# 03_Mos.net
KiCad netlist of a schematic drawn in Altium Designer
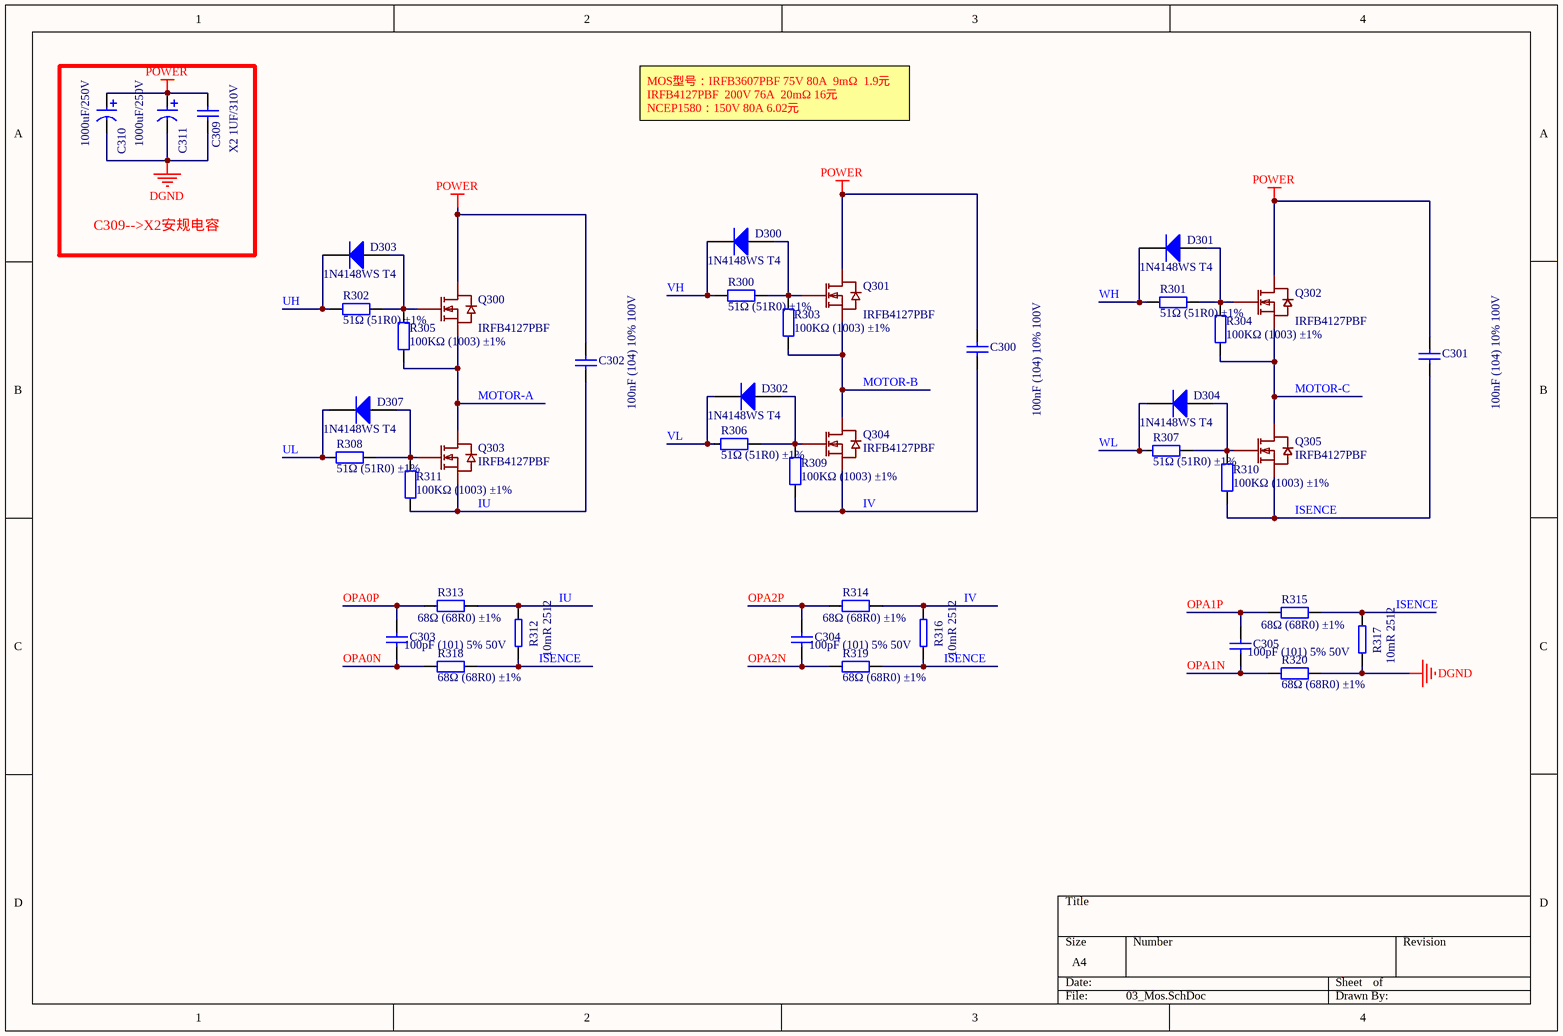
[diagram p0: 03_Mos.SchDoc]

(export (version "E")
  (design (tool "Eeschema 10.0.6"))
  (components
    (comp (ref "C300")
      (value "100nF (104) 10% 100V")
      (footprint "1206_C")
      (description "贴片电容")
      (libsource (lib "Miscellaneous Devices LC") (part "1206 100nF (104) 10% 50V"))
    )
    (comp (ref "C301")
      (value "100nF (104) 10% 100V")
      (footprint "1206_C")
      (description "贴片电容")
      (libsource (lib "Miscellaneous Devices LC") (part "1206 100nF (104) 10% 50V"))
    )
    (comp (ref "C302")
      (value "100nF (104) 10% 100V")
      (footprint "1206_C")
      (description "贴片电容")
      (libsource (lib "Miscellaneous Devices LC") (part "1206 100nF (104) 10% 50V"))
    )
    (comp (ref "C303")
      (value "100pF (101) 5% 50V")
      (footprint "0805_C")
      (description "贴片电容")
      (libsource (lib "Miscellaneous Devices LC") (part "0805 100pF (101) 5% 50V"))
    )
    (comp (ref "C304")
      (value "100pF (101) 5% 50V")
      (footprint "0805_C")
      (description "贴片电容")
      (libsource (lib "Miscellaneous Devices LC") (part "0805 100pF (101) 5% 50V"))
    )
    (comp (ref "C305")
      (value "100pF (101) 5% 50V")
      (footprint "0805_C")
      (description "贴片电容")
      (libsource (lib "Miscellaneous Devices LC") (part "0805 100pF (101) 5% 50V"))
    )
    (comp (ref "C309")
      (value "X2 1UF/310V")
      (footprint "X2 1UF 310V")
      (description "贴片电容")
      (libsource (lib "Miscellaneous Devices LC") (part "1206 100nF (104) 10% 50V"))
    )
    (comp (ref "C310")
      (value "1000uF/250V")
      (footprint "1000uf/250V")
      (description "电解电容")
      (libsource (lib "Schlibv2") (part "CAP2"))
    )
    (comp (ref "C311")
      (value "1000uF/250V")
      (footprint "1000uf/250V")
      (description "电解电容")
      (libsource (lib "Schlibv2") (part "CAP2"))
    )
    (comp (ref "D300")
      (value "1N4148WS T4")
      (footprint "SOD-323")
      (description "二极管")
      (libsource (lib "Miscellaneous Devices LC") (part "SOD-323 1N4148WS T4"))
    )
    (comp (ref "D301")
      (value "1N4148WS T4")
      (footprint "SOD-323")
      (description "二极管")
      (libsource (lib "Miscellaneous Devices LC") (part "SOD-323 1N4148WS T4"))
    )
    (comp (ref "D302")
      (value "1N4148WS T4")
      (footprint "SOD-323")
      (description "二极管")
      (libsource (lib "Miscellaneous Devices LC") (part "SOD-323 1N4148WS T4"))
    )
    (comp (ref "D303")
      (value "1N4148WS T4")
      (footprint "SOD-323")
      (description "二极管")
      (libsource (lib "Miscellaneous Devices LC") (part "SOD-323 1N4148WS T4"))
    )
    (comp (ref "D304")
      (value "1N4148WS T4")
      (footprint "SOD-323")
      (description "二极管")
      (libsource (lib "Miscellaneous Devices LC") (part "SOD-323 1N4148WS T4"))
    )
    (comp (ref "D307")
      (value "1N4148WS T4")
      (footprint "SOD-323")
      (description "二极管")
      (libsource (lib "Miscellaneous Devices LC") (part "SOD-323 1N4148WS T4"))
    )
    (comp (ref "Q300")
      (value "IRFB4127PBF")
      (footprint "IRFB4127")
      (libsource (lib "RayPCB20210502") (part "IRFB4127PBF"))
    )
    (comp (ref "Q301")
      (value "IRFB4127PBF")
      (footprint "IRFB4127")
      (libsource (lib "RayPCB20210502") (part "IRFB4127PBF"))
    )
    (comp (ref "Q302")
      (value "IRFB4127PBF")
      (footprint "IRFB4127")
      (libsource (lib "RayPCB20210502") (part "IRFB4127PBF"))
    )
    (comp (ref "Q303")
      (value "IRFB4127PBF")
      (footprint "IRFB4127")
      (libsource (lib "RayPCB20210502") (part "IRFB4127PBF"))
    )
    (comp (ref "Q304")
      (value "IRFB4127PBF")
      (footprint "IRFB4127")
      (libsource (lib "RayPCB20210502") (part "IRFB4127PBF"))
    )
    (comp (ref "Q305")
      (value "IRFB4127PBF")
      (footprint "IRFB4127")
      (libsource (lib "RayPCB20210502") (part "IRFB4127PBF"))
    )
    (comp (ref "R300")
      (value "51Ω (51R0) ±1%")
      (footprint "0805_R")
      (description "贴片电阻")
      (libsource (lib "Miscellaneous Devices LC") (part "0805 51Ω (51R0) 1%"))
    )
    (comp (ref "R301")
      (value "51Ω (51R0) ±1%")
      (footprint "0805_R")
      (description "贴片电阻")
      (libsource (lib "Miscellaneous Devices LC") (part "0805 51Ω (51R0) 1%"))
    )
    (comp (ref "R302")
      (value "51Ω (51R0) ±1%")
      (footprint "0805_R")
      (description "贴片电阻")
      (libsource (lib "Miscellaneous Devices LC") (part "0805 51Ω (51R0) 1%"))
    )
    (comp (ref "R303")
      (value "100KΩ (1003) ±1%")
      (footprint "0805_R")
      (description "贴片电阻")
      (libsource (lib "Miscellaneous Devices LC") (part "0805 100KΩ (1003) 1%"))
    )
    (comp (ref "R304")
      (value "100KΩ (1003) ±1%")
      (footprint "0805_R")
      (description "贴片电阻")
      (libsource (lib "Miscellaneous Devices LC") (part "0805 100KΩ (1003) 1%"))
    )
    (comp (ref "R305")
      (value "100KΩ (1003) ±1%")
      (footprint "0805_R")
      (description "贴片电阻")
      (libsource (lib "Miscellaneous Devices LC") (part "0805 100KΩ (1003) 1%"))
    )
    (comp (ref "R306")
      (value "51Ω (51R0) ±1%")
      (footprint "0805_R")
      (description "贴片电阻")
      (libsource (lib "Miscellaneous Devices LC") (part "0805 51Ω (51R0) 1%"))
    )
    (comp (ref "R307")
      (value "51Ω (51R0) ±1%")
      (footprint "0805_R")
      (description "贴片电阻")
      (libsource (lib "Miscellaneous Devices LC") (part "0805 51Ω (51R0) 1%"))
    )
    (comp (ref "R308")
      (value "51Ω (51R0) ±1%")
      (footprint "0805_R")
      (description "贴片电阻")
      (libsource (lib "Miscellaneous Devices LC") (part "0805 51Ω (51R0) 1%"))
    )
    (comp (ref "R309")
      (value "100KΩ (1003) ±1%")
      (footprint "0805_R")
      (description "贴片电阻")
      (libsource (lib "Miscellaneous Devices LC") (part "0805 100KΩ (1003) 1%"))
    )
    (comp (ref "R310")
      (value "100KΩ (1003) ±1%")
      (footprint "0805_R")
      (description "贴片电阻")
      (libsource (lib "Miscellaneous Devices LC") (part "0805 100KΩ (1003) 1%"))
    )
    (comp (ref "R311")
      (value "100KΩ (1003) ±1%")
      (footprint "0805_R")
      (description "贴片电阻")
      (libsource (lib "Miscellaneous Devices LC") (part "0805 100KΩ (1003) 1%"))
    )
    (comp (ref "R312")
      (value "10mR 2512")
      (footprint "R2512")
      (libsource (lib "RayPCB20210502") (part "Res10K"))
    )
    (comp (ref "R313")
      (value "68Ω (68R0) ±1%")
      (footprint "0805_R")
      (description "贴片电阻")
      (libsource (lib "Miscellaneous Devices LC") (part "0805 68Ω (68R0) 1%"))
    )
    (comp (ref "R314")
      (value "68Ω (68R0) ±1%")
      (footprint "0805_R")
      (description "贴片电阻")
      (libsource (lib "Miscellaneous Devices LC") (part "0805 68Ω (68R0) 1%"))
    )
    (comp (ref "R315")
      (value "68Ω (68R0) ±1%")
      (footprint "0805_R")
      (description "贴片电阻")
      (libsource (lib "Miscellaneous Devices LC") (part "0805 68Ω (68R0) 1%"))
    )
    (comp (ref "R316")
      (value "10mR 2512")
      (footprint "R2512")
      (libsource (lib "RayPCB20210502") (part "Res10K"))
    )
    (comp (ref "R317")
      (value "10mR 2512")
      (footprint "R2512")
      (libsource (lib "RayPCB20210502") (part "Res10K"))
    )
    (comp (ref "R318")
      (value "68Ω (68R0) ±1%")
      (footprint "0805_R")
      (description "贴片电阻")
      (libsource (lib "Miscellaneous Devices LC") (part "0805 68Ω (68R0) 1%"))
    )
    (comp (ref "R319")
      (value "68Ω (68R0) ±1%")
      (footprint "0805_R")
      (description "贴片电阻")
      (libsource (lib "Miscellaneous Devices LC") (part "0805 68Ω (68R0) 1%"))
    )
    (comp (ref "R320")
      (value "68Ω (68R0) ±1%")
      (footprint "0805_R")
      (description "贴片电阻")
      (libsource (lib "Miscellaneous Devices LC") (part "0805 68Ω (68R0) 1%"))
    )
  )
  (nets
    (net (code "1") (name "/ISENCE") (class "Default")
      (node (ref "C301") (pin "1") (pinfunction "1_1") (pintype "passive"))
      (node (ref "Q305") (pin "3") (pinfunction "S_3") (pintype "passive"))
      (node (ref "R310") (pin "1") (pinfunction "1_1") (pintype "passive"))
      (node (ref "R312") (pin "1") (pintype "passive"))
      (node (ref "R315") (pin "2") (pinfunction "2_2") (pintype "passive"))
      (node (ref "R316") (pin "1") (pintype "passive"))
      (node (ref "R317") (pin "2") (pintype "passive"))
      (node (ref "R318") (pin "2") (pinfunction "2_2") (pintype "passive"))
      (node (ref "R319") (pin "2") (pinfunction "2_2") (pintype "passive"))
    )
    (net (code "2") (name "/IU") (class "Default")
      (node (ref "C302") (pin "1") (pinfunction "1_1") (pintype "passive"))
      (node (ref "Q303") (pin "3") (pinfunction "S_3") (pintype "passive"))
      (node (ref "R311") (pin "1") (pinfunction "1_1") (pintype "passive"))
      (node (ref "R312") (pin "2") (pintype "passive"))
      (node (ref "R313") (pin "2") (pinfunction "2_2") (pintype "passive"))
    )
    (net (code "3") (name "/IV") (class "Default")
      (node (ref "C300") (pin "1") (pinfunction "1_1") (pintype "passive"))
      (node (ref "Q304") (pin "3") (pinfunction "S_3") (pintype "passive"))
      (node (ref "R309") (pin "1") (pinfunction "1_1") (pintype "passive"))
      (node (ref "R314") (pin "2") (pinfunction "2_2") (pintype "passive"))
      (node (ref "R316") (pin "2") (pintype "passive"))
    )
    (net (code "4") (name "/MOTOR-A") (class "Default")
      (node (ref "Q300") (pin "3") (pinfunction "S_3") (pintype "passive"))
      (node (ref "Q303") (pin "2") (pinfunction "D_2") (pintype "passive"))
      (node (ref "R305") (pin "1") (pinfunction "1_1") (pintype "passive"))
    )
    (net (code "5") (name "/MOTOR-B") (class "Default")
      (node (ref "Q301") (pin "3") (pinfunction "S_3") (pintype "passive"))
      (node (ref "Q304") (pin "2") (pinfunction "D_2") (pintype "passive"))
      (node (ref "R303") (pin "1") (pinfunction "1_1") (pintype "passive"))
    )
    (net (code "6") (name "/MOTOR-C") (class "Default")
      (node (ref "Q302") (pin "3") (pinfunction "S_3") (pintype "passive"))
      (node (ref "Q305") (pin "2") (pinfunction "D_2") (pintype "passive"))
      (node (ref "R304") (pin "1") (pinfunction "1_1") (pintype "passive"))
    )
    (net (code "7") (name "/OPA0N") (class "Default")
      (node (ref "C303") (pin "1") (pinfunction "1_1") (pintype "passive"))
      (node (ref "R318") (pin "1") (pinfunction "1_1") (pintype "passive"))
    )
    (net (code "8") (name "/OPA0P") (class "Default")
      (node (ref "C303") (pin "2") (pinfunction "2_2") (pintype "passive"))
      (node (ref "R313") (pin "1") (pinfunction "1_1") (pintype "passive"))
    )
    (net (code "9") (name "/OPA1N") (class "Default")
      (node (ref "C305") (pin "1") (pinfunction "1_1") (pintype "passive"))
      (node (ref "R320") (pin "1") (pinfunction "1_1") (pintype "passive"))
    )
    (net (code "10") (name "/OPA1P") (class "Default")
      (node (ref "C305") (pin "2") (pinfunction "2_2") (pintype "passive"))
      (node (ref "R315") (pin "1") (pinfunction "1_1") (pintype "passive"))
    )
    (net (code "11") (name "/OPA2N") (class "Default")
      (node (ref "C304") (pin "1") (pinfunction "1_1") (pintype "passive"))
      (node (ref "R319") (pin "1") (pinfunction "1_1") (pintype "passive"))
    )
    (net (code "12") (name "/OPA2P") (class "Default")
      (node (ref "C304") (pin "2") (pinfunction "2_2") (pintype "passive"))
      (node (ref "R314") (pin "1") (pinfunction "1_1") (pintype "passive"))
    )
    (net (code "13") (name "/UH") (class "Default")
      (node (ref "D303") (pin "2") (pinfunction "K_2") (pintype "passive"))
      (node (ref "R302") (pin "1") (pinfunction "1_1") (pintype "passive"))
    )
    (net (code "14") (name "/UL") (class "Default")
      (node (ref "D307") (pin "2") (pinfunction "K_2") (pintype "passive"))
      (node (ref "R308") (pin "1") (pinfunction "1_1") (pintype "passive"))
    )
    (net (code "15") (name "/VH") (class "Default")
      (node (ref "D300") (pin "2") (pinfunction "K_2") (pintype "passive"))
      (node (ref "R300") (pin "1") (pinfunction "1_1") (pintype "passive"))
    )
    (net (code "16") (name "/VL") (class "Default")
      (node (ref "D302") (pin "2") (pinfunction "K_2") (pintype "passive"))
      (node (ref "R306") (pin "1") (pinfunction "1_1") (pintype "passive"))
    )
    (net (code "17") (name "/WH") (class "Default")
      (node (ref "D301") (pin "2") (pinfunction "K_2") (pintype "passive"))
      (node (ref "R301") (pin "1") (pinfunction "1_1") (pintype "passive"))
    )
    (net (code "18") (name "/WL") (class "Default")
      (node (ref "D304") (pin "2") (pinfunction "K_2") (pintype "passive"))
      (node (ref "R307") (pin "1") (pinfunction "1_1") (pintype "passive"))
    )
    (net (code "19") (name "DGND") (class "Default")
      (node (ref "C309") (pin "1") (pinfunction "1_1") (pintype "passive"))
      (node (ref "C310") (pin "2") (pintype "passive"))
      (node (ref "C311") (pin "2") (pintype "passive"))
      (node (ref "R317") (pin "1") (pintype "passive"))
      (node (ref "R320") (pin "2") (pinfunction "2_2") (pintype "passive"))
    )
    (net (code "20") (name "Net-(D300-A)") (class "Default")
      (node (ref "D300") (pin "1") (pinfunction "A_1") (pintype "passive"))
      (node (ref "Q301") (pin "1") (pinfunction "G_1") (pintype "passive"))
      (node (ref "R300") (pin "2") (pinfunction "2_2") (pintype "passive"))
      (node (ref "R303") (pin "2") (pinfunction "2_2") (pintype "passive"))
    )
    (net (code "21") (name "Net-(D301-A)") (class "Default")
      (node (ref "D301") (pin "1") (pinfunction "A_1") (pintype "passive"))
      (node (ref "Q302") (pin "1") (pinfunction "G_1") (pintype "passive"))
      (node (ref "R301") (pin "2") (pinfunction "2_2") (pintype "passive"))
      (node (ref "R304") (pin "2") (pinfunction "2_2") (pintype "passive"))
    )
    (net (code "22") (name "Net-(D302-A)") (class "Default")
      (node (ref "D302") (pin "1") (pinfunction "A_1") (pintype "passive"))
      (node (ref "Q304") (pin "1") (pinfunction "G_1") (pintype "passive"))
      (node (ref "R306") (pin "2") (pinfunction "2_2") (pintype "passive"))
      (node (ref "R309") (pin "2") (pinfunction "2_2") (pintype "passive"))
    )
    (net (code "23") (name "Net-(D303-A)") (class "Default")
      (node (ref "D303") (pin "1") (pinfunction "A_1") (pintype "passive"))
      (node (ref "Q300") (pin "1") (pinfunction "G_1") (pintype "passive"))
      (node (ref "R302") (pin "2") (pinfunction "2_2") (pintype "passive"))
      (node (ref "R305") (pin "2") (pinfunction "2_2") (pintype "passive"))
    )
    (net (code "24") (name "Net-(D304-A)") (class "Default")
      (node (ref "D304") (pin "1") (pinfunction "A_1") (pintype "passive"))
      (node (ref "Q305") (pin "1") (pinfunction "G_1") (pintype "passive"))
      (node (ref "R307") (pin "2") (pinfunction "2_2") (pintype "passive"))
      (node (ref "R310") (pin "2") (pinfunction "2_2") (pintype "passive"))
    )
    (net (code "25") (name "Net-(D307-A)") (class "Default")
      (node (ref "D307") (pin "1") (pinfunction "A_1") (pintype "passive"))
      (node (ref "Q303") (pin "1") (pinfunction "G_1") (pintype "passive"))
      (node (ref "R308") (pin "2") (pinfunction "2_2") (pintype "passive"))
      (node (ref "R311") (pin "2") (pinfunction "2_2") (pintype "passive"))
    )
    (net (code "26") (name "POWER") (class "Default")
      (node (ref "C300") (pin "2") (pinfunction "2_2") (pintype "passive"))
      (node (ref "C301") (pin "2") (pinfunction "2_2") (pintype "passive"))
      (node (ref "C302") (pin "2") (pinfunction "2_2") (pintype "passive"))
      (node (ref "C309") (pin "2") (pinfunction "2_2") (pintype "passive"))
      (node (ref "C310") (pin "1") (pintype "passive"))
      (node (ref "C311") (pin "1") (pintype "passive"))
      (node (ref "Q300") (pin "2") (pinfunction "D_2") (pintype "passive"))
      (node (ref "Q301") (pin "2") (pinfunction "D_2") (pintype "passive"))
      (node (ref "Q302") (pin "2") (pinfunction "D_2") (pintype "passive"))
    )
  )
)
